# DC_DC_Power.net
KiCad netlist of a schematic drawn in Altium Designer
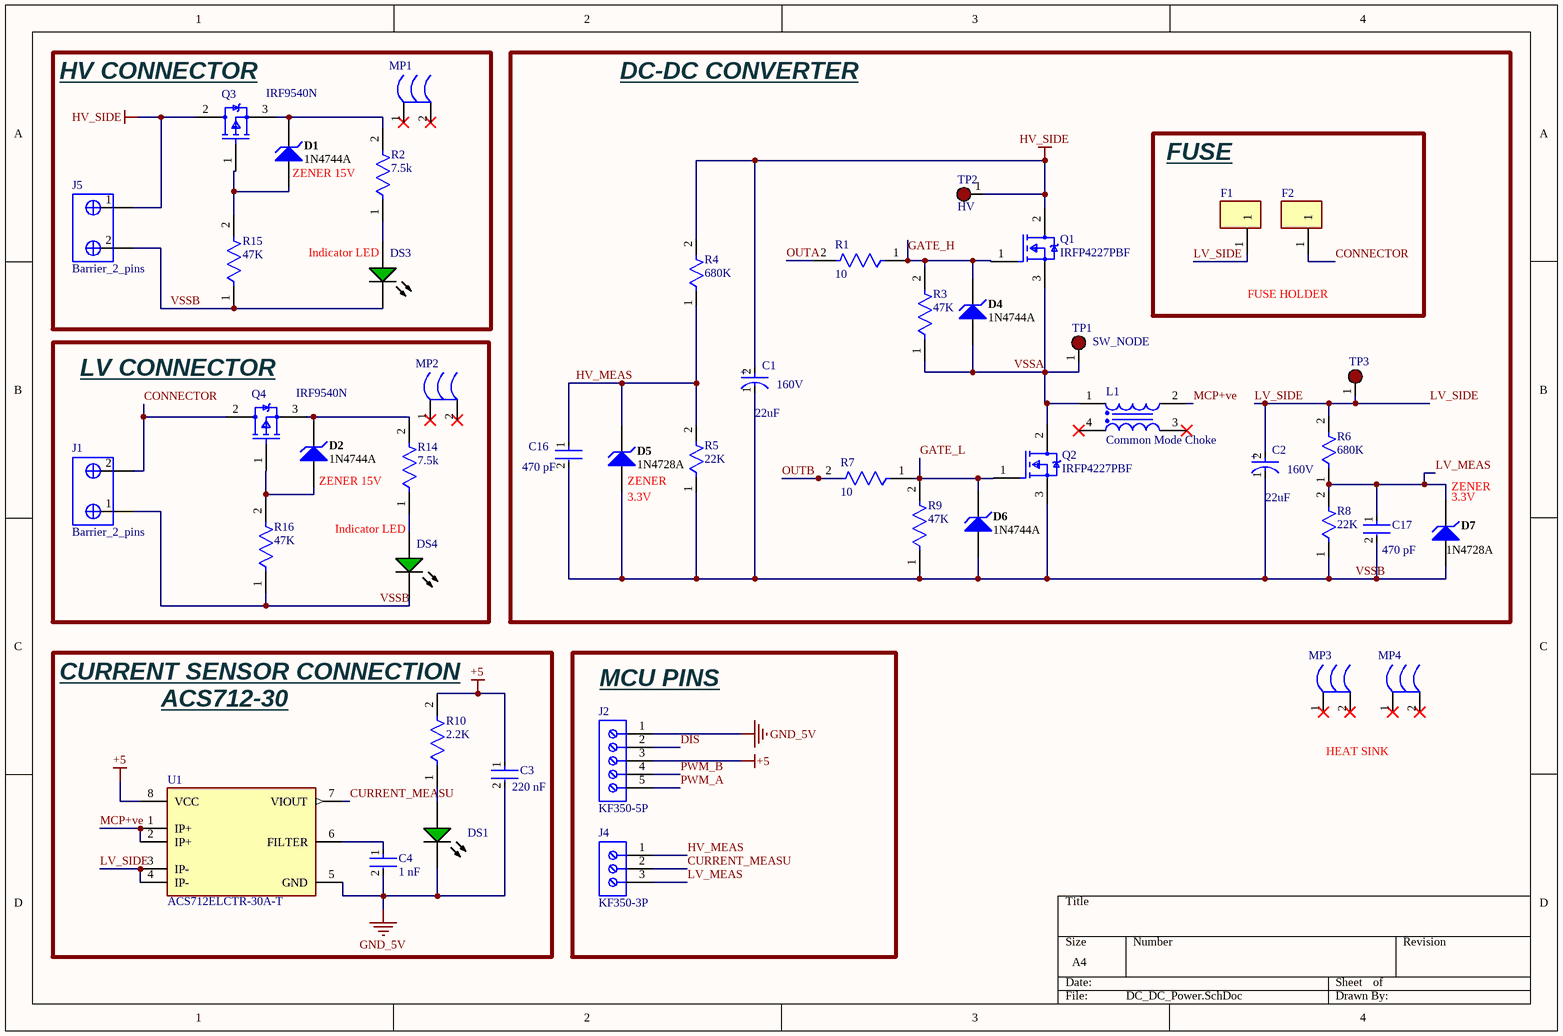
[diagram p0: DC_DC_Power.SchDoc]

(export (version "E")
  (design (tool "Eeschema 10.0.6"))
  (components
    (comp (ref "C1")
      (value "22uF")
      (footprint "FP-RAD-TH-D_18_0_5-L_31_5-MFG")
      (description "Aluminum Electrolytic Capacitors (Radial Lead Type) 330uF ±20% 160V")
      (fields (field (name "TOLERANCE") "20%") (field (name "VOLTAGE") "160V"))
      (libsource (lib "Altium Content Vault") (part "e7731fe20d7b760a41a604414fa9837"))
    )
    (comp (ref "C2")
      (value "22uF")
      (footprint "FP-RAD-TH-D_18_0_5-L_31_5-MFG")
      (description "Aluminum Electrolytic Capacitors (Radial Lead Type) 330uF ±20% 160V")
      (fields (field (name "TOLERANCE") "20%") (field (name "VOLTAGE") "160V"))
      (libsource (lib "Altium Content Vault") (part "e7731fe20d7b760a41a604414fa9837"))
    )
    (comp (ref "C3")
      (value "220 nF")
      (footprint "FP-C0805C-DN-MFG")
      (description "CAP CER 0.22UF 50V X7R 0805")
      (fields
        (field (name "MANUFACTURER") "KEMET")
        (field (name "OCTOPART") "https://octopart.com/c0805c224k5ractu-kemet-144670")
      )
      (libsource (lib "Altium Content Vault") (part "b4654b650e69147ec39a6b967a45e02"))
    )
    (comp (ref "C4")
      (value "1 nF")
      (footprint "FP-C0805C-DN-MFG")
      (description "CAP CER 0.22UF 50V X7R 0805")
      (fields
        (field (name "MANUFACTURER") "KEMET")
        (field (name "OCTOPART") "https://octopart.com/c0805c224k5ractu-kemet-144670")
      )
      (libsource (lib "Altium Content Vault") (part "b4654b650e69147ec39a6b967a45e02"))
    )
    (comp (ref "C16")
      (value "470 pF")
      (footprint "FP-C0805C-DN-MFG")
      (description "CAP CER 0.22UF 50V X7R 0805")
      (fields
        (field (name "MANUFACTURER") "KEMET")
        (field (name "OCTOPART") "https://octopart.com/c0805c224k5ractu-kemet-144670")
      )
      (libsource (lib "Altium Content Vault") (part "b4654b650e69147ec39a6b967a45e02"))
    )
    (comp (ref "C17")
      (value "470 pF")
      (footprint "FP-C0805C-DN-MFG")
      (description "CAP CER 0.22UF 50V X7R 0805")
      (fields
        (field (name "MANUFACTURER") "KEMET")
        (field (name "OCTOPART") "https://octopart.com/c0805c224k5ractu-kemet-144670")
      )
      (libsource (lib "Altium Content Vault") (part "b4654b650e69147ec39a6b967a45e02"))
    )
    (comp (ref "D1")
      (value "1N4744A")
      (footprint "FAIR-DO-41-2_V")
      (description "Zener Diode, 15V, 1W, 5%, -65 to 200 degC, 2-Pin DO-41, Body 2.72 x 5.2 mm, RoHS")
      (fields (field (name "MANUFACTURER") "Fairchild Semiconductor") (field (name "TOLERANCE") "5%"))
      (libsource (lib "Altium Content Vault") (part "FAIR-DZEN-A1K2-2"))
    )
    (comp (ref "D2")
      (value "1N4744A")
      (footprint "FAIR-DO-41-2_V")
      (description "Zener Diode, 15V, 1W, 5%, -65 to 200 degC, 2-Pin DO-41, Body 2.72 x 5.2 mm, RoHS")
      (fields (field (name "MANUFACTURER") "Fairchild Semiconductor") (field (name "TOLERANCE") "5%"))
      (libsource (lib "Altium Content Vault") (part "FAIR-DZEN-A1K2-2"))
    )
    (comp (ref "D4")
      (value "1N4744A")
      (footprint "FAIR-DO-41-2_V")
      (description "Zener Diode, 15V, 1W, 5%, -65 to 200 degC, 2-Pin DO-41, Body 2.72 x 5.2 mm, RoHS")
      (fields (field (name "MANUFACTURER") "Fairchild Semiconductor") (field (name "TOLERANCE") "5%"))
      (libsource (lib "Altium Content Vault") (part "FAIR-DZEN-A1K2-2"))
    )
    (comp (ref "D5")
      (value "1N4728A")
      (footprint "FAIR-DO-41-2_V")
      (description "Zener Diode, 3.3V, 1W, 5%, -65 to 200 degC, 2-Pin DO-41, Body 2.72 x 5.2 mm, RoHS")
      (fields (field (name "MANUFACTURER") "Fairchild Semiconductor") (field (name "TOLERANCE") "5%"))
      (libsource (lib "Altium Content Vault") (part "FAIR-DZEN-A1K2-2"))
    )
    (comp (ref "D6")
      (value "1N4744A")
      (footprint "FAIR-DO-41-2_V")
      (description "Zener Diode, 15V, 1W, 5%, -65 to 200 degC, 2-Pin DO-41, Body 2.72 x 5.2 mm, RoHS")
      (fields (field (name "MANUFACTURER") "Fairchild Semiconductor") (field (name "TOLERANCE") "5%"))
      (libsource (lib "Altium Content Vault") (part "FAIR-DZEN-A1K2-2"))
    )
    (comp (ref "D7")
      (value "1N4728A")
      (footprint "FAIR-DO-41-2_V")
      (description "Zener Diode, 3.3V, 1W, 5%, -65 to 200 degC, 2-Pin DO-41, Body 2.72 x 5.2 mm, RoHS")
      (fields (field (name "MANUFACTURER") "Fairchild Semiconductor") (field (name "TOLERANCE") "5%"))
      (libsource (lib "Altium Content Vault") (part "FAIR-DZEN-A1K2-2"))
    )
    (comp (ref "DS1")
      (value "HSMG-C170")
      (footprint "AVAG-HSMX-C170_V")
      (description "Chip LED, Green, 2.2 V, -40 to 85 degC, 2-Pin SMD, Pb-Free, Tape and Reel")
      (fields (field (name "MANUFACTURER") "Avago"))
      (libsource (lib "Altium Content Vault") (part "LED_GREEN_A1K2-2"))
    )
    (comp (ref "DS3")
      (value "HSMG-C170")
      (footprint "AVAG-HSMX-C170_V")
      (description "Chip LED, Green, 2.2 V, -40 to 85 degC, 2-Pin SMD, Pb-Free, Tape and Reel")
      (fields (field (name "MANUFACTURER") "Avago"))
      (libsource (lib "Altium Content Vault") (part "LED_GREEN_A1K2-2"))
    )
    (comp (ref "DS4")
      (value "HSMG-C170")
      (footprint "AVAG-HSMX-C170_V")
      (description "Chip LED, Green, 2.2 V, -40 to 85 degC, 2-Pin SMD, Pb-Free, Tape and Reel")
      (fields (field (name "MANUFACTURER") "Avago"))
      (libsource (lib "Altium Content Vault") (part "LED_GREEN_A1K2-2"))
    )
    (comp (ref "F1")
      (value "0751.0110")
      (footprint "FP-0751_0110-MFG")
      (description "FUSE CLIP CARTRIDGE 10A PCB")
      (fields
        (field (name "OCTOPART") "https://octopart.com/0751.0110-schurter-19402")
        (field (name "MANUFACTURER") "Schurter")
      )
      (libsource (lib "Altium Content Vault") (part "6594cd1380bf084bed0a40489f8b218"))
    )
    (comp (ref "F2")
      (value "0751.0110")
      (footprint "FP-0751_0110-MFG")
      (description "FUSE CLIP CARTRIDGE 10A PCB")
      (fields
        (field (name "OCTOPART") "https://octopart.com/0751.0110-schurter-19402")
        (field (name "MANUFACTURER") "Schurter")
      )
      (libsource (lib "Altium Content Vault") (part "6594cd1380bf084bed0a40489f8b218"))
    )
    (comp (ref "J1")
      (value "Barrier_2_pins")
      (footprint "PCBComponent_1")
      (libsource (lib "Barrier Terminal 9.5mm 2-Pins") (part "Barrier_2_pins"))
    )
    (comp (ref "J2")
      (value "KF350-5P")
      (footprint "PCBComponent_1")
      (libsource (lib "KF350-3..5mm-5P") (part "KF350-5P"))
    )
    (comp (ref "J4")
      (value "KF350-3P")
      (footprint "PCBComponent_1")
      (libsource (lib "KF350-3P") (part "KF350-3P"))
    )
    (comp (ref "J5")
      (value "Barrier_2_pins")
      (footprint "PCBComponent_1")
      (libsource (lib "Barrier Terminal 9.5mm 2-Pins") (part "Barrier_2_pins"))
    )
    (comp (ref "L1")
      (value "Common Mode Choke")
      (footprint "PCBComponent_1")
      (libsource (lib "R6123-X425_Choke") (part "T60405-R6123-X425"))
    )
    (comp (ref "MP1")
      (value "Heat Sink")
      (footprint "PCBComponent_1")
      (libsource (lib "Heat Sink 34_12_25") (part "Heat Sink"))
    )
    (comp (ref "MP2")
      (value "Heat Sink")
      (footprint "PCBComponent_1")
      (libsource (lib "Heat Sink 34_12_25") (part "Heat Sink"))
    )
    (comp (ref "MP3")
      (value "Heat Sink")
      (footprint "PCBComponent_1")
      (libsource (lib "Heat Sink 34_12_25") (part "Heat Sink"))
    )
    (comp (ref "MP4")
      (value "Heat Sink")
      (footprint "PCBComponent_1")
      (libsource (lib "Heat Sink 34_12_25") (part "Heat Sink"))
    )
    (comp (ref "Q1")
      (value "IRFP4227PBF")
      (footprint "FP-PG-TO247-3-MFG")
      (description "MOSFET N-CH 200V 65A TO247AC")
      (libsource (lib "Altium Content Vault") (part "8b62d417cbef8344eebe0bde0c45977"))
    )
    (comp (ref "Q2")
      (value "IRFP4227PBF")
      (footprint "FP-PG-TO247-3-MFG")
      (description "MOSFET N-CH 200V 65A TO247AC")
      (libsource (lib "Altium Content Vault") (part "8b62d417cbef8344eebe0bde0c45977"))
    )
    (comp (ref "Q3")
      (value "IRF9540N")
      (footprint "PCBComponent_1")
      (libsource (lib "IRF9540N") (part "IRF9540N"))
    )
    (comp (ref "Q4")
      (value "IRF9540N")
      (footprint "PCBComponent_1")
      (libsource (lib "IRF9540N") (part "IRF9540N"))
    )
    (comp (ref "R1")
      (value "10")
      (footprint "FP-RC0805-0_6-IPC_C")
      (description "33  1/8W   0805")
      (fields (field (name "TOLERANCE") "1%"))
      (libsource (lib "Altium Content Vault") (part "1029c3af85768c4190bb7ad29bc67b5"))
    )
    (comp (ref "R2")
      (value "7.5k")
      (footprint "FP-RC0805-0_6-IPC_C")
      (description "7.5K  1/8W   0805")
      (fields (field (name "TOLERANCE") "1%"))
      (libsource (lib "Altium Content Vault") (part "1029c3af85768c4190bb7ad29bc67b5"))
    )
    (comp (ref "R3")
      (value "47K")
      (footprint "FP-RC0805-0_6-IPC_C")
      (description "47K  1/8W   0805")
      (fields (field (name "TOLERANCE") "1%"))
      (libsource (lib "Altium Content Vault") (part "1029c3af85768c4190bb7ad29bc67b5"))
    )
    (comp (ref "R4")
      (value "680K")
      (footprint "PCBComponent_1")
      (libsource (lib "RES_0.125W_AXIAL") (part "RES"))
    )
    (comp (ref "R5")
      (value "22K")
      (footprint "PCBComponent_1")
      (libsource (lib "RES_0.125W_AXIAL") (part "RES"))
    )
    (comp (ref "R6")
      (value "680K")
      (footprint "PCBComponent_1")
      (libsource (lib "RES_0.125W_AXIAL") (part "RES"))
    )
    (comp (ref "R7")
      (value "10")
      (footprint "FP-RC0805-0_6-IPC_C")
      (description "33  1/8W   0805")
      (fields (field (name "TOLERANCE") "1%"))
      (libsource (lib "Altium Content Vault") (part "1029c3af85768c4190bb7ad29bc67b5"))
    )
    (comp (ref "R8")
      (value "22K")
      (footprint "PCBComponent_1")
      (libsource (lib "RES_0.125W_AXIAL") (part "RES"))
    )
    (comp (ref "R9")
      (value "47K")
      (footprint "FP-RC0805-0_6-IPC_C")
      (description "47K  1/8W   0805")
      (fields (field (name "TOLERANCE") "1%"))
      (libsource (lib "Altium Content Vault") (part "1029c3af85768c4190bb7ad29bc67b5"))
    )
    (comp (ref "R10")
      (value "2.2K")
      (footprint "FP-RC0805-0_6-IPC_C")
      (description "2.2K  1/8W   0805")
      (fields (field (name "TOLERANCE") "1%"))
      (libsource (lib "Altium Content Vault") (part "1029c3af85768c4190bb7ad29bc67b5"))
    )
    (comp (ref "R14")
      (value "7.5k")
      (footprint "FP-RC0805-0_6-IPC_C")
      (description "7.5K  1/8W   0805")
      (fields (field (name "TOLERANCE") "1%"))
      (libsource (lib "Altium Content Vault") (part "1029c3af85768c4190bb7ad29bc67b5"))
    )
    (comp (ref "R15")
      (value "47K")
      (footprint "FP-RC0805-0_6-IPC_C")
      (description "47K  1/8W   0805")
      (fields (field (name "TOLERANCE") "1%"))
      (libsource (lib "Altium Content Vault") (part "1029c3af85768c4190bb7ad29bc67b5"))
    )
    (comp (ref "R16")
      (value "47K")
      (footprint "FP-RC0805-0_6-IPC_C")
      (description "47K  1/8W   0805")
      (fields (field (name "TOLERANCE") "1%"))
      (libsource (lib "Altium Content Vault") (part "1029c3af85768c4190bb7ad29bc67b5"))
    )
    (comp (ref "TP1")
      (value "SW_NODE")
      (footprint "PCBComponent_1")
      (description "Test Point, Miniature, Red, TH")
      (libsource (lib "Test_Pin_RED") (part "TP"))
    )
    (comp (ref "TP2")
      (value "HV")
      (footprint "PCBComponent_1")
      (description "Test Point, Miniature, Red, TH")
      (libsource (lib "Test_Pin_RED") (part "TP"))
    )
    (comp (ref "TP3")
      (value "LV")
      (footprint "PCBComponent_1")
      (description "Test Point, Miniature, Red, TH")
      (libsource (lib "Test_Pin_RED") (part "TP"))
    )
    (comp (ref "U1")
      (value "ACS712ELCTR-30A-T")
      (footprint "FP-LC-8-IPC_C")
      (description "SENSOR CURRENT HALL 30A AC/DC")
      (libsource (lib "Altium Content Vault") (part "a0faa98973ef06dd62ff869f1199b2d"))
    )
  )
  (nets
    (net (code "1") (name "+5") (class "Default")
      (node (ref "C3") (pin "1") (pinfunction "1_1") (pintype "passive"))
      (node (ref "J2") (pin "3") (pinfunction "3_3") (pintype "passive"))
      (node (ref "R10") (pin "2") (pinfunction "2_2") (pintype "passive"))
      (node (ref "U1") (pin "8") (pinfunction "VCC_8") (pintype "power_in"))
    )
    (net (code "2") (name "/CONNECTOR") (class "Default")
      (node (ref "F2") (pin "1") (pinfunction "1_1") (pintype "passive"))
      (node (ref "J1") (pin "2") (pinfunction "2_2") (pintype "passive"))
      (node (ref "Q4") (pin "2") (pinfunction "Drain_2") (pintype "passive"))
    )
    (net (code "3") (name "/CURRENT_MEASU") (class "Default")
      (node (ref "J4") (pin "2") (pinfunction "2_2") (pintype "passive"))
      (node (ref "U1") (pin "7") (pinfunction "VIOUT_7") (pintype "output"))
    )
    (net (code "4") (name "/DIS") (class "Default")
      (node (ref "J2") (pin "2") (pinfunction "2_2") (pintype "passive"))
    )
    (net (code "5") (name "/GATE_H") (class "Default")
      (node (ref "D4") (pin "2") (pinfunction "K_2") (pintype "passive"))
      (node (ref "Q1") (pin "1") (pinfunction "GATE_1") (pintype "passive"))
      (node (ref "R1") (pin "1") (pinfunction "1_1") (pintype "passive"))
      (node (ref "R3") (pin "2") (pinfunction "2_2") (pintype "passive"))
    )
    (net (code "6") (name "/GATE_L") (class "Default")
      (node (ref "D6") (pin "2") (pinfunction "K_2") (pintype "passive"))
      (node (ref "Q2") (pin "1") (pinfunction "GATE_1") (pintype "passive"))
      (node (ref "R7") (pin "1") (pinfunction "1_1") (pintype "passive"))
      (node (ref "R9") (pin "2") (pinfunction "2_2") (pintype "passive"))
    )
    (net (code "7") (name "/HV_MEAS") (class "Default")
      (node (ref "C16") (pin "1") (pinfunction "1_1") (pintype "passive"))
      (node (ref "D5") (pin "2") (pinfunction "K_2") (pintype "passive"))
      (node (ref "J4") (pin "1") (pinfunction "1_1") (pintype "passive"))
      (node (ref "R4") (pin "1") (pinfunction "1_1") (pintype "passive"))
      (node (ref "R5") (pin "2") (pinfunction "2_2") (pintype "passive"))
    )
    (net (code "8") (name "/LV_MEAS") (class "Default")
      (node (ref "C17") (pin "1") (pinfunction "1_1") (pintype "passive"))
      (node (ref "D7") (pin "2") (pinfunction "K_2") (pintype "passive"))
      (node (ref "J4") (pin "3") (pinfunction "3_3") (pintype "passive"))
      (node (ref "R6") (pin "1") (pinfunction "1_1") (pintype "passive"))
      (node (ref "R8") (pin "2") (pinfunction "2_2") (pintype "passive"))
    )
    (net (code "9") (name "/LV_SIDE") (class "Default")
      (node (ref "C2") (pin "2") (pinfunction "A_2") (pintype "passive"))
      (node (ref "F1") (pin "1") (pinfunction "1_1") (pintype "passive"))
      (node (ref "R6") (pin "2") (pinfunction "2_2") (pintype "passive"))
      (node (ref "TP3") (pin "1") (pinfunction "1_1") (pintype "passive"))
      (node (ref "U1") (pin "3") (pinfunction "IP-_3") (pintype "passive"))
      (node (ref "U1") (pin "4") (pinfunction "IP-_4") (pintype "passive"))
    )
    (net (code "10") (name "/MCP+ve") (class "Default")
      (node (ref "L1") (pin "2") (pinfunction "4_2") (pintype "passive"))
      (node (ref "U1") (pin "1") (pinfunction "IP+_1") (pintype "passive"))
      (node (ref "U1") (pin "2") (pinfunction "IP+_2") (pintype "passive"))
    )
    (net (code "11") (name "/OUTA") (class "Default")
      (node (ref "R1") (pin "2") (pinfunction "2_2") (pintype "passive"))
    )
    (net (code "12") (name "/OUTB") (class "Default")
      (node (ref "R7") (pin "2") (pinfunction "2_2") (pintype "passive"))
    )
    (net (code "13") (name "/PWM_A") (class "Default")
      (node (ref "J2") (pin "5") (pinfunction "5_5") (pintype "passive"))
    )
    (net (code "14") (name "/PWM_B") (class "Default")
      (node (ref "J2") (pin "4") (pinfunction "4_4") (pintype "passive"))
    )
    (net (code "15") (name "/VSSA") (class "Default")
      (node (ref "D4") (pin "1") (pinfunction "A_1") (pintype "passive"))
      (node (ref "L1") (pin "1") (pinfunction "1_1") (pintype "passive"))
      (node (ref "Q1") (pin "3") (pinfunction "SOURCE_3") (pintype "passive"))
      (node (ref "Q2") (pin "2") (pinfunction "DRAIN_2") (pintype "passive"))
      (node (ref "R3") (pin "1") (pinfunction "1_1") (pintype "passive"))
      (node (ref "TP1") (pin "1") (pinfunction "1_1") (pintype "passive"))
    )
    (net (code "16") (name "/VSSB") (class "Default")
      (node (ref "C1") (pin "1") (pinfunction "C_1") (pintype "passive"))
      (node (ref "C16") (pin "2") (pinfunction "2_2") (pintype "passive"))
      (node (ref "C17") (pin "2") (pinfunction "2_2") (pintype "passive"))
      (node (ref "C2") (pin "1") (pinfunction "C_1") (pintype "passive"))
      (node (ref "D5") (pin "1") (pinfunction "A_1") (pintype "passive"))
      (node (ref "D6") (pin "1") (pinfunction "A_1") (pintype "passive"))
      (node (ref "D7") (pin "1") (pinfunction "A_1") (pintype "passive"))
      (node (ref "DS3") (pin "2") (pinfunction "K_2") (pintype "passive"))
      (node (ref "DS4") (pin "2") (pinfunction "K_2") (pintype "passive"))
      (node (ref "J1") (pin "1") (pinfunction "1_1") (pintype "passive"))
      (node (ref "J5") (pin "2") (pinfunction "2_2") (pintype "passive"))
      (node (ref "Q2") (pin "3") (pinfunction "SOURCE_3") (pintype "passive"))
      (node (ref "R15") (pin "1") (pinfunction "1_1") (pintype "passive"))
      (node (ref "R16") (pin "1") (pinfunction "1_1") (pintype "passive"))
      (node (ref "R5") (pin "1") (pinfunction "1_1") (pintype "passive"))
      (node (ref "R8") (pin "1") (pinfunction "1_1") (pintype "passive"))
      (node (ref "R9") (pin "1") (pinfunction "1_1") (pintype "passive"))
    )
    (net (code "17") (name "GND_5V") (class "Default")
      (node (ref "C3") (pin "2") (pinfunction "2_2") (pintype "passive"))
      (node (ref "C4") (pin "2") (pinfunction "2_2") (pintype "passive"))
      (node (ref "DS1") (pin "2") (pinfunction "K_2") (pintype "passive"))
      (node (ref "J2") (pin "1") (pinfunction "1_1") (pintype "passive"))
      (node (ref "U1") (pin "5") (pinfunction "GND_5") (pintype "power_in"))
    )
    (net (code "18") (name "HV_SIDE") (class "Default")
      (node (ref "C1") (pin "2") (pinfunction "A_2") (pintype "passive"))
      (node (ref "J5") (pin "1") (pinfunction "1_1") (pintype "passive"))
      (node (ref "Q1") (pin "2") (pinfunction "DRAIN_2") (pintype "passive"))
      (node (ref "Q3") (pin "2") (pinfunction "Drain_2") (pintype "passive"))
      (node (ref "R4") (pin "2") (pinfunction "2_2") (pintype "passive"))
      (node (ref "TP2") (pin "1") (pinfunction "1_1") (pintype "passive"))
    )
    (net (code "19") (name "Net-(D1-A)") (class "Default")
      (node (ref "D1") (pin "1") (pinfunction "A_1") (pintype "passive"))
      (node (ref "Q3") (pin "1") (pinfunction "Gate_1") (pintype "passive"))
      (node (ref "R15") (pin "2") (pinfunction "2_2") (pintype "passive"))
    )
    (net (code "20") (name "Net-(D1-K)") (class "Default")
      (node (ref "D1") (pin "2") (pinfunction "K_2") (pintype "passive"))
      (node (ref "Q3") (pin "3") (pinfunction "Source_3") (pintype "passive"))
      (node (ref "R2") (pin "2") (pinfunction "2_2") (pintype "passive"))
    )
    (net (code "21") (name "Net-(D2-A)") (class "Default")
      (node (ref "D2") (pin "1") (pinfunction "A_1") (pintype "passive"))
      (node (ref "Q4") (pin "1") (pinfunction "Gate_1") (pintype "passive"))
      (node (ref "R16") (pin "2") (pinfunction "2_2") (pintype "passive"))
    )
    (net (code "22") (name "Net-(D2-K)") (class "Default")
      (node (ref "D2") (pin "2") (pinfunction "K_2") (pintype "passive"))
      (node (ref "Q4") (pin "3") (pinfunction "Source_3") (pintype "passive"))
      (node (ref "R14") (pin "2") (pinfunction "2_2") (pintype "passive"))
    )
    (net (code "23") (name "Net-(DS1-A)") (class "Default")
      (node (ref "DS1") (pin "1") (pinfunction "A_1") (pintype "passive"))
      (node (ref "R10") (pin "1") (pinfunction "1_1") (pintype "passive"))
    )
    (net (code "24") (name "Net-(DS3-A)") (class "Default")
      (node (ref "DS3") (pin "1") (pinfunction "A_1") (pintype "passive"))
      (node (ref "R2") (pin "1") (pinfunction "1_1") (pintype "passive"))
    )
    (net (code "25") (name "Net-(DS4-A)") (class "Default")
      (node (ref "DS4") (pin "1") (pinfunction "A_1") (pintype "passive"))
      (node (ref "R14") (pin "1") (pinfunction "1_1") (pintype "passive"))
    )
    (net (code "26") (name "Net-(U1-FILTER)") (class "Default")
      (node (ref "C4") (pin "1") (pinfunction "1_1") (pintype "passive"))
      (node (ref "U1") (pin "6") (pinfunction "FILTER_6") (pintype "passive"))
    )
    (net (code "27") (name "unconnected-(L1-2-Pad4)") (class "Default")
      (node (ref "L1") (pin "4") (pinfunction "2_4") (pintype "passive+no_connect"))
    )
    (net (code "28") (name "unconnected-(L1-Pad3)") (class "Default")
      (node (ref "L1") (pin "3") (pinfunction "3_3") (pintype "passive+no_connect"))
    )
    (net (code "29") (name "unconnected-(MP1-Pad1)") (class "Default")
      (node (ref "MP1") (pin "1") (pinfunction "1_1") (pintype "passive+no_connect"))
    )
    (net (code "30") (name "unconnected-(MP1-Pad2)") (class "Default")
      (node (ref "MP1") (pin "2") (pinfunction "2_2") (pintype "passive+no_connect"))
    )
    (net (code "31") (name "unconnected-(MP2-Pad1)") (class "Default")
      (node (ref "MP2") (pin "1") (pinfunction "1_1") (pintype "passive+no_connect"))
    )
    (net (code "32") (name "unconnected-(MP2-Pad2)") (class "Default")
      (node (ref "MP2") (pin "2") (pinfunction "2_2") (pintype "passive+no_connect"))
    )
    (net (code "33") (name "unconnected-(MP3-Pad1)") (class "Default")
      (node (ref "MP3") (pin "1") (pinfunction "1_1") (pintype "passive"))
    )
    (net (code "34") (name "unconnected-(MP3-Pad2)") (class "Default")
      (node (ref "MP3") (pin "2") (pinfunction "2_2") (pintype "passive+no_connect"))
    )
    (net (code "35") (name "unconnected-(MP4-Pad1)") (class "Default")
      (node (ref "MP4") (pin "1") (pinfunction "1_1") (pintype "passive+no_connect"))
    )
    (net (code "36") (name "unconnected-(MP4-Pad2)") (class "Default")
      (node (ref "MP4") (pin "2") (pinfunction "2_2") (pintype "passive+no_connect"))
    )
  )
)
